# Top.net
KiCad netlist of a schematic drawn in Altium Designer
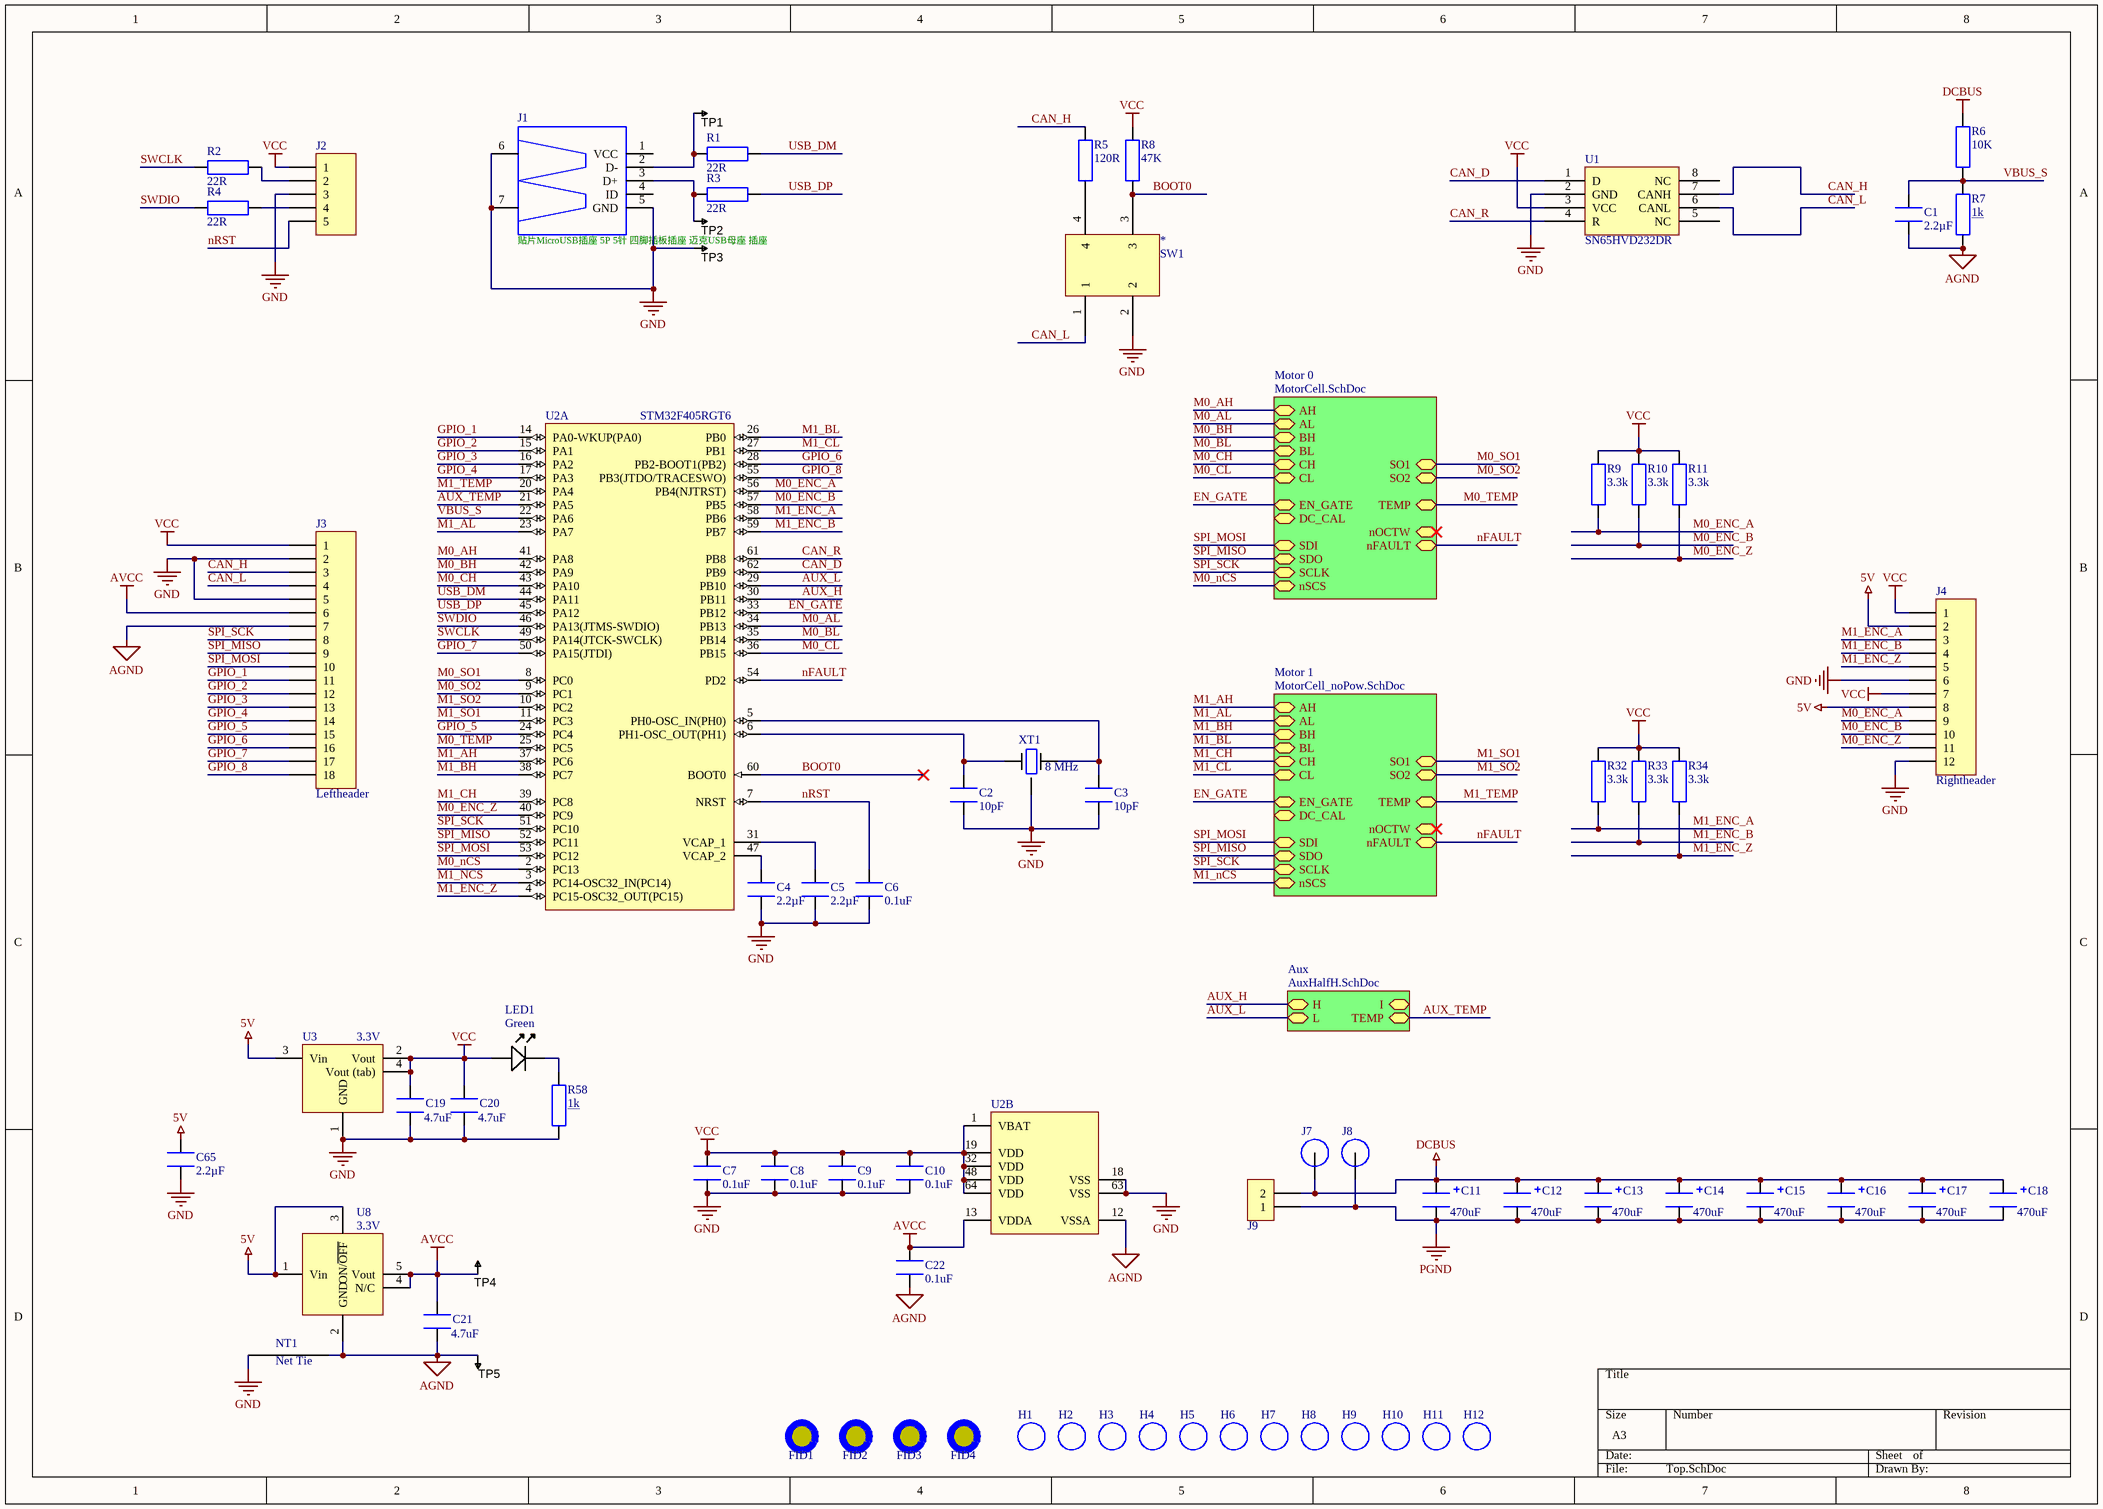
[diagram p0: Top.SchDoc]

(export (version "E")
  (design (tool "Eeschema 10.0.6"))
  (components
    (comp (ref "*")
      (value "SW1")
      (footprint "switch_2")
      (libsource (lib "CustomComponents") (part "Switch_2"))
    )
    (comp (ref "C1")
      (value "2.2µF")
      (footprint "CAPC1608X09L")
      (description "CAP CER 2.2UF 16V X5R 0603")
      (fields
        (field (name "MANUFACTURER") "Murata Electronics North America")
        (field (name "MANUFACTURER PART NUMBER") "GRM188R61C225KE15D")
      )
      (libsource (lib "CustomComponents") (part "GRM188R61C225KE15D"))
    )
    (comp (ref "C2")
      (value "10pF")
      (footprint "CAPC1608X09L")
      (description "CAP CER 10PF 50V NP0 0603")
      (fields
        (field (name "MANUFACTURER") "Murata Electronics North America")
        (field (name "MANUFACTURER PART NUMBER") "GRM1885C1H100JA01D")
      )
      (libsource (lib "CustomComponents") (part "GRM1885C1H100JA01D"))
    )
    (comp (ref "C3")
      (value "10pF")
      (footprint "CAPC1608X09L")
      (description "CAP CER 10PF 50V NP0 0603")
      (fields
        (field (name "MANUFACTURER") "Murata Electronics North America")
        (field (name "MANUFACTURER PART NUMBER") "GRM1885C1H100JA01D")
      )
      (libsource (lib "CustomComponents") (part "GRM1885C1H100JA01D"))
    )
    (comp (ref "C4")
      (value "2.2µF")
      (footprint "CAPC1608X09L")
      (description "CAP CER 2.2UF 16V X5R 0603")
      (fields
        (field (name "MANUFACTURER") "Murata Electronics North America")
        (field (name "MANUFACTURER PART NUMBER") "GRM188R61C225KE15D")
      )
      (libsource (lib "CustomComponents") (part "GRM188R61C225KE15D"))
    )
    (comp (ref "C5")
      (value "2.2µF")
      (footprint "CAPC1608X09L")
      (description "CAP CER 2.2UF 16V X5R 0603")
      (fields
        (field (name "MANUFACTURER") "Murata Electronics North America")
        (field (name "MANUFACTURER PART NUMBER") "GRM188R61C225KE15D")
      )
      (libsource (lib "CustomComponents") (part "GRM188R61C225KE15D"))
    )
    (comp (ref "C6")
      (value "0.1uF")
      (footprint "CAPC1608X09L")
      (description "CAP CER 0.1UF 50V X7R 0603")
      (fields
        (field (name "MANUFACTURER") "Murata Electronics North America")
        (field (name "MANUFACTURER PART NUMBER") "GRM188R71H104KA93D")
      )
      (libsource (lib "CustomComponents") (part "GRM188R71H104KA93D"))
    )
    (comp (ref "C7")
      (value "0.1uF")
      (footprint "CAPC1608X09L")
      (description "CAP CER 0.1UF 50V X7R 0603")
      (fields
        (field (name "MANUFACTURER") "Murata Electronics North America")
        (field (name "MANUFACTURER PART NUMBER") "GRM188R71H104KA93D")
      )
      (libsource (lib "CustomComponents") (part "GRM188R71H104KA93D"))
    )
    (comp (ref "C8")
      (value "0.1uF")
      (footprint "CAPC1608X09L")
      (description "CAP CER 0.1UF 50V X7R 0603")
      (fields
        (field (name "MANUFACTURER") "Murata Electronics North America")
        (field (name "MANUFACTURER PART NUMBER") "GRM188R71H104KA93D")
      )
      (libsource (lib "CustomComponents") (part "GRM188R71H104KA93D"))
    )
    (comp (ref "C9")
      (value "0.1uF")
      (footprint "CAPC1608X09L")
      (description "CAP CER 0.1UF 50V X7R 0603")
      (fields
        (field (name "MANUFACTURER") "Murata Electronics North America")
        (field (name "MANUFACTURER PART NUMBER") "GRM188R71H104KA93D")
      )
      (libsource (lib "CustomComponents") (part "GRM188R71H104KA93D"))
    )
    (comp (ref "C10")
      (value "0.1uF")
      (footprint "CAPC1608X09L")
      (description "CAP CER 0.1UF 50V X7R 0603")
      (fields
        (field (name "MANUFACTURER") "Murata Electronics North America")
        (field (name "MANUFACTURER PART NUMBER") "GRM188R71H104KA93D")
      )
      (libsource (lib "CustomComponents") (part "GRM188R71H104KA93D"))
    )
    (comp (ref "C11")
      (value "470uF")
      (footprint "CAP_ELEC_SIZE_G")
      (description "CAP, FP Series, 470 µF, 25 V, Radial Can - SMD, 10 mm")
      (fields
        (field (name "MANUFACTURER") "Panasonic Electronic Components")
        (field (name "TOLERANCE") "?0%")
      )
      (libsource (lib "CustomComponents") (part "EEEFP1E471AP"))
    )
    (comp (ref "C12")
      (value "470uF")
      (footprint "CAP_ELEC_SIZE_G")
      (description "CAP, FP Series, 470 µF, 25 V, Radial Can - SMD, 10 mm")
      (fields
        (field (name "MANUFACTURER") "Panasonic Electronic Components")
        (field (name "TOLERANCE") "?0%")
      )
      (libsource (lib "CustomComponents") (part "EEEFP1E471AP"))
    )
    (comp (ref "C13")
      (value "470uF")
      (footprint "CAP_ELEC_SIZE_G")
      (description "CAP, FP Series, 470 µF, 25 V, Radial Can - SMD, 10 mm")
      (fields
        (field (name "MANUFACTURER") "Panasonic Electronic Components")
        (field (name "TOLERANCE") "?0%")
      )
      (libsource (lib "CustomComponents") (part "EEEFP1E471AP"))
    )
    (comp (ref "C14")
      (value "470uF")
      (footprint "CAP_ELEC_SIZE_G")
      (description "CAP, FP Series, 470 µF, 25 V, Radial Can - SMD, 10 mm")
      (fields
        (field (name "MANUFACTURER") "Panasonic Electronic Components")
        (field (name "TOLERANCE") "?0%")
      )
      (libsource (lib "CustomComponents") (part "EEEFP1E471AP"))
    )
    (comp (ref "C15")
      (value "470uF")
      (footprint "CAP_ELEC_SIZE_G")
      (description "CAP, FP Series, 470 µF, 25 V, Radial Can - SMD, 10 mm")
      (fields
        (field (name "MANUFACTURER") "Panasonic Electronic Components")
        (field (name "TOLERANCE") "?0%")
      )
      (libsource (lib "CustomComponents") (part "EEEFP1E471AP"))
    )
    (comp (ref "C16")
      (value "470uF")
      (footprint "CAP_ELEC_SIZE_G")
      (description "CAP, FP Series, 470 µF, 25 V, Radial Can - SMD, 10 mm")
      (fields
        (field (name "MANUFACTURER") "Panasonic Electronic Components")
        (field (name "TOLERANCE") "?0%")
      )
      (libsource (lib "CustomComponents") (part "EEEFP1E471AP"))
    )
    (comp (ref "C17")
      (value "470uF")
      (footprint "CAP_ELEC_SIZE_G")
      (description "CAP, FP Series, 470 µF, 25 V, Radial Can - SMD, 10 mm")
      (fields
        (field (name "MANUFACTURER") "Panasonic Electronic Components")
        (field (name "TOLERANCE") "?0%")
      )
      (libsource (lib "CustomComponents") (part "EEEFP1E471AP"))
    )
    (comp (ref "C18")
      (value "470uF")
      (footprint "CAP_ELEC_SIZE_G")
      (description "CAP, FP Series, 470 µF, 25 V, Radial Can - SMD, 10 mm")
      (fields
        (field (name "MANUFACTURER") "Panasonic Electronic Components")
        (field (name "TOLERANCE") "?0%")
      )
      (libsource (lib "CustomComponents") (part "EEEFP1E471AP"))
    )
    (comp (ref "C19")
      (value "4.7uF")
      (footprint "CAPC2012X09N")
      (description "CAP CER 4.7UF 35V X5R 0805")
      (fields
        (field (name "MANUFACTURER") "Murata Electronics North America")
        (field (name "TOLERANCE") "?0%")
      )
      (libsource (lib "CustomComponents") (part "GRM219R6YA475KA73D"))
    )
    (comp (ref "C20")
      (value "4.7uF")
      (footprint "CAPC2012X09N")
      (description "CAP CER 4.7UF 35V X5R 0805")
      (fields
        (field (name "MANUFACTURER") "Murata Electronics North America")
        (field (name "TOLERANCE") "?0%")
      )
      (libsource (lib "CustomComponents") (part "GRM219R6YA475KA73D"))
    )
    (comp (ref "C21")
      (value "4.7uF")
      (footprint "CAPC2012X09N")
      (description "CAP CER 4.7UF 35V X5R 0805")
      (fields
        (field (name "MANUFACTURER") "Murata Electronics North America")
        (field (name "TOLERANCE") "?0%")
      )
      (libsource (lib "CustomComponents") (part "GRM219R6YA475KA73D"))
    )
    (comp (ref "C22")
      (value "0.1uF")
      (footprint "CAPC1608X09L")
      (description "CAP CER 0.1UF 50V X7R 0603")
      (fields
        (field (name "MANUFACTURER") "Murata Electronics North America")
        (field (name "MANUFACTURER PART NUMBER") "GRM188R71H104KA93D")
      )
      (libsource (lib "CustomComponents") (part "GRM188R71H104KA93D"))
    )
    (comp (ref "C65")
      (value "2.2µF")
      (footprint "CAPC1608X09L")
      (description "CAP CER 2.2UF 16V X5R 0603")
      (fields
        (field (name "MANUFACTURER") "Murata Electronics North America")
        (field (name "MANUFACTURER PART NUMBER") "GRM188R61C225KE15D")
      )
      (libsource (lib "CustomComponents") (part "GRM188R61C225KE15D"))
    )
    (comp (ref "FID1")
      (value "FIDUCIAL")
      (footprint "FIDUCIAL")
      (description "1mm Fiducial with 2mm soldermask, 3mm keepout")
      (libsource (lib "CustomComponents") (part "FIDUCIAL"))
    )
    (comp (ref "FID2")
      (value "FIDUCIAL")
      (footprint "FIDUCIAL")
      (description "1mm Fiducial with 2mm soldermask, 3mm keepout")
      (libsource (lib "CustomComponents") (part "FIDUCIAL"))
    )
    (comp (ref "FID3")
      (value "FIDUCIAL")
      (footprint "FIDUCIAL")
      (description "1mm Fiducial with 2mm soldermask, 3mm keepout")
      (libsource (lib "CustomComponents") (part "FIDUCIAL"))
    )
    (comp (ref "FID4")
      (value "FIDUCIAL")
      (footprint "FIDUCIAL")
      (description "1mm Fiducial with 2mm soldermask, 3mm keepout")
      (libsource (lib "CustomComponents") (part "FIDUCIAL"))
    )
    (comp (ref "H1")
      (value "~")
      (footprint "M3 Hole")
      (description "M3 Hole with no copper")
      (libsource (lib "CustomComponents") (part "M3 Hole"))
    )
    (comp (ref "H2")
      (value "~")
      (footprint "M3 Hole")
      (description "M3 Hole with no copper")
      (libsource (lib "CustomComponents") (part "M3 Hole"))
    )
    (comp (ref "H3")
      (value "~")
      (footprint "M3 Hole")
      (description "M3 Hole with no copper")
      (libsource (lib "CustomComponents") (part "M3 Hole"))
    )
    (comp (ref "H4")
      (value "~")
      (footprint "M3 Hole")
      (description "M3 Hole with no copper")
      (libsource (lib "CustomComponents") (part "M3 Hole"))
    )
    (comp (ref "H5")
      (value "~")
      (footprint "M3 Hole")
      (description "M3 Hole with no copper")
      (libsource (lib "CustomComponents") (part "M3 Hole"))
    )
    (comp (ref "H6")
      (value "~")
      (footprint "M3 Hole")
      (description "M3 Hole with no copper")
      (libsource (lib "CustomComponents") (part "M3 Hole"))
    )
    (comp (ref "H7")
      (value "~")
      (footprint "M3 Hole")
      (description "M3 Hole with no copper")
      (libsource (lib "CustomComponents") (part "M3 Hole"))
    )
    (comp (ref "H8")
      (value "~")
      (footprint "M3 Hole")
      (description "M3 Hole with no copper")
      (libsource (lib "CustomComponents") (part "M3 Hole"))
    )
    (comp (ref "H9")
      (value "~")
      (footprint "M3 Hole")
      (description "M3 Hole with no copper")
      (libsource (lib "CustomComponents") (part "M3 Hole"))
    )
    (comp (ref "H10")
      (value "~")
      (footprint "M3 Hole")
      (description "M3 Hole with no copper")
      (libsource (lib "CustomComponents") (part "M3 Hole"))
    )
    (comp (ref "H11")
      (value "~")
      (footprint "M3 Hole")
      (description "M3 Hole with no copper")
      (libsource (lib "CustomComponents") (part "M3 Hole"))
    )
    (comp (ref "H12")
      (value "~")
      (footprint "M3 Hole")
      (description "M3 Hole with no copper")
      (libsource (lib "CustomComponents") (part "M3 Hole"))
    )
    (comp (ref "J1")
      (value "贴片MicroUSB插座 5P 5针 四脚插板插座 迈克USB母座 插座")
      (footprint "Micro_USB")
      (libsource (lib "*") (part "USB_1_1"))
    )
    (comp (ref "J2")
      (value "~")
      (footprint "HDR1X5")
      (description "Header, 5-Pin")
      (fields (field (name "PUBLISHER") "Altium Limited"))
      (libsource (lib "Miscellaneous Connectors") (part "Header 5"))
    )
    (comp (ref "J3")
      (value "Leftheader")
      (footprint "HDR1X18")
      (description "Header, 18-Pin")
      (fields (field (name "PUBLISHER") "Altium Limited"))
      (libsource (lib "Miscellaneous Connectors") (part "Header 18"))
    )
    (comp (ref "J4")
      (value "Rightheader")
      (footprint "HDR1X12")
      (description "Header, 12-Pin")
      (fields (field (name "PUBLISHER") "Altium Limited"))
      (libsource (lib "Miscellaneous Connectors") (part "Header 12"))
    )
    (comp (ref "J7")
      (value "~")
      (footprint "M3 Spade Hole")
      (description "M3 Spade Terminal")
      (libsource (lib "CustomComponents") (part "M3 Spade Terminal"))
    )
    (comp (ref "J8")
      (value "~")
      (footprint "M3 Spade Hole")
      (description "M3 Spade Terminal")
      (libsource (lib "CustomComponents") (part "M3 Spade Terminal"))
    )
    (comp (ref "J9")
      (value "1868076")
      (footprint "1868076")
      (description "CONN TERM BLOCK 2POS 7.62MM")
      (fields (field (name "MANUFACTURER") "Phoenix Contact") (field (name "VOLTAGE") "300V"))
      (libsource (lib "CustomComponents") (part "1868076"))
    )
    (comp (ref "LED1")
      (value "Green")
      (footprint "LED-0603-GREEN")
      (description "LED GREEN CLEAR 0603 SMD")
      (fields
        (field (name "MANUFACTURER") "Lite-On Inc.")
        (field (name "MANUFACTURER PART NUMBER") "LTST-C190KGKT")
      )
      (libsource (lib "CustomComponents") (part "LTST-C190KGKT"))
    )
    (comp (ref "NT1")
      (value "~")
      (footprint "NetTie_2mm")
      (libsource (lib "CustomComponents") (part "NetTie_2mm"))
    )
    (comp (ref "R1")
      (value "22R")
      (footprint "RESC1608X55N")
      (description "RES SMD 22 OHM 1% 1/10W 0603")
      (fields
        (field (name "MANUFACTURER") "Yageo")
        (field (name "MANUFACTURER PART NUMBER") "RC0603FR-0722RL")
      )
      (libsource (lib "CustomComponents") (part "RC0603FR-0722RL"))
    )
    (comp (ref "R2")
      (value "22R")
      (footprint "RESC1608X55N")
      (description "RES SMD 22 OHM 1% 1/10W 0603")
      (fields
        (field (name "MANUFACTURER") "Yageo")
        (field (name "MANUFACTURER PART NUMBER") "RC0603FR-0722RL")
      )
      (libsource (lib "CustomComponents") (part "RC0603FR-0722RL"))
    )
    (comp (ref "R3")
      (value "22R")
      (footprint "RESC1608X55N")
      (description "RES SMD 22 OHM 1% 1/10W 0603")
      (fields
        (field (name "MANUFACTURER") "Yageo")
        (field (name "MANUFACTURER PART NUMBER") "RC0603FR-0722RL")
      )
      (libsource (lib "CustomComponents") (part "RC0603FR-0722RL"))
    )
    (comp (ref "R4")
      (value "22R")
      (footprint "RESC1608X55N")
      (description "RES SMD 22 OHM 1% 1/10W 0603")
      (fields
        (field (name "MANUFACTURER") "Yageo")
        (field (name "MANUFACTURER PART NUMBER") "RC0603FR-0722RL")
      )
      (libsource (lib "CustomComponents") (part "RC0603FR-0722RL"))
    )
    (comp (ref "R5")
      (value "120R")
      (footprint "RESC1608X55N")
      (description "RES SMD 120 OHM 1% 1/10W 0603")
      (fields
        (field (name "MANUFACTURER") "Yageo")
        (field (name "MANUFACTURER PART NUMBER") "RC0603FR-07120RL")
      )
      (libsource (lib "CustomComponents") (part "RC0603FR-07120RL"))
    )
    (comp (ref "R6")
      (value "10K")
      (footprint "RESC1608X55N")
      (description "RES SMD 10K OHM 1% 1/10W 0603")
      (fields
        (field (name "MANUFACTURER") "Yageo")
        (field (name "MANUFACTURER PART NUMBER") "RC0603FR-0710KL")
      )
      (libsource (lib "CustomComponents") (part "RC0603FR-0710KL"))
    )
    (comp (ref "R7")
      (value "1k")
      (footprint "RESC1608X55N")
      (description "RES SMD 1K OHM 1% 1/10W 0603")
      (fields (field (name "MANUFACTURER") "Yageo") (field (name "TOLERANCE") "?%"))
      (libsource (lib "CustomComponents") (part "RC0603FR-071KL"))
    )
    (comp (ref "R8")
      (value "47K")
      (footprint "RESC1608X55N")
      (description "RES SMD 47K OHM 1% 1/10W 0603")
      (fields
        (field (name "MANUFACTURER") "Yageo")
        (field (name "MANUFACTURER PART NUMBER") "RC0603FR-0747KL")
      )
      (libsource (lib "CustomComponents") (part "RC0603FR-0747KL"))
    )
    (comp (ref "R9")
      (value "3.3k")
      (footprint "RESC1608X55N")
      (description "RES SMD 3.3K OHM 1% 1/10W 0603")
      (fields (field (name "MANUFACTURER") "Yageo") (field (name "TOLERANCE") "?%"))
      (libsource (lib "CustomComponents") (part "RC0603FR-073K3L"))
    )
    (comp (ref "R10")
      (value "3.3k")
      (footprint "RESC1608X55N")
      (description "RES SMD 3.3K OHM 1% 1/10W 0603")
      (fields (field (name "MANUFACTURER") "Yageo") (field (name "TOLERANCE") "?%"))
      (libsource (lib "CustomComponents") (part "RC0603FR-073K3L"))
    )
    (comp (ref "R11")
      (value "3.3k")
      (footprint "RESC1608X55N")
      (description "RES SMD 3.3K OHM 1% 1/10W 0603")
      (fields (field (name "MANUFACTURER") "Yageo") (field (name "TOLERANCE") "?%"))
      (libsource (lib "CustomComponents") (part "RC0603FR-073K3L"))
    )
    (comp (ref "R32")
      (value "3.3k")
      (footprint "RESC1608X55N")
      (description "RES SMD 3.3K OHM 1% 1/10W 0603")
      (fields (field (name "MANUFACTURER") "Yageo") (field (name "TOLERANCE") "?%"))
      (libsource (lib "CustomComponents") (part "RC0603FR-073K3L"))
    )
    (comp (ref "R33")
      (value "3.3k")
      (footprint "RESC1608X55N")
      (description "RES SMD 3.3K OHM 1% 1/10W 0603")
      (fields (field (name "MANUFACTURER") "Yageo") (field (name "TOLERANCE") "?%"))
      (libsource (lib "CustomComponents") (part "RC0603FR-073K3L"))
    )
    (comp (ref "R34")
      (value "3.3k")
      (footprint "RESC1608X55N")
      (description "RES SMD 3.3K OHM 1% 1/10W 0603")
      (fields (field (name "MANUFACTURER") "Yageo") (field (name "TOLERANCE") "?%"))
      (libsource (lib "CustomComponents") (part "RC0603FR-073K3L"))
    )
    (comp (ref "R58")
      (value "1k")
      (footprint "RESC1608X55N")
      (description "RES SMD 1K OHM 1% 1/10W 0603")
      (fields (field (name "MANUFACTURER") "Yageo") (field (name "TOLERANCE") "?%"))
      (libsource (lib "CustomComponents") (part "RC0603FR-071KL"))
    )
    (comp (ref "TP1")
      (value "TESTPOINT")
      (footprint "TP-R60")
      (description "SMD test pin")
      (libsource (lib "PBL - Test Points") (part "TESTPOINT"))
    )
    (comp (ref "TP2")
      (value "TESTPOINT")
      (footprint "TP-R60")
      (description "SMD test pin")
      (libsource (lib "PBL - Test Points") (part "TESTPOINT"))
    )
    (comp (ref "TP3")
      (value "TESTPOINT")
      (footprint "TP-R60")
      (description "SMD test pin")
      (libsource (lib "PBL - Test Points") (part "TESTPOINT"))
    )
    (comp (ref "TP4")
      (value "TESTPOINT")
      (footprint "TP-R30")
      (description "SMD test pin")
      (libsource (lib "PBL - Test Points") (part "TESTPOINT"))
    )
    (comp (ref "TP5")
      (value "TESTPOINT")
      (footprint "TP-R30")
      (description "SMD test pin")
      (libsource (lib "PBL - Test Points") (part "TESTPOINT"))
    )
    (comp (ref "U1")
      (value "SN65HVD232D")
      (footprint "SOIC127P600X175-8N")
      (fields
        (field (name "MANUFACTURER") "Texas Instruments")
        (field (name "MANUFACTURER PART NUMBER") "SN65HVD232DR")
      )
      (libsource (lib "CustomComponents") (part "SN65HVD232D"))
    )
    (comp (ref "U2")
      (value "~")
      (footprint "STM-LQFP64_N")
      (fields (field (name "MANUFACTURER") "STMicroelectronics") (field (name "PARTNUMBER") "STM32F405RGT6"))
      (libsource (lib "STMicroelectronics STM32 F4") (part "STM32F405RGT6"))
    )
    (comp (ref "U3")
      (value "3.3V")
      (footprint "SOT223")
      (description "IC REG LDO 3.3V 1A SOT223")
      (fields (field (name "MANUFACTURER") "Diodes Incorporated"))
      (libsource (lib "CustomComponents") (part "AZ1117EH-3.3TRG1"))
    )
    (comp (ref "U8")
      (value "3.3V")
      (footprint "SOT23-5")
      (description "IC REG LDO 3.3V 0.25A SOT23-5")
      (fields (field (name "MANUFACTURER") "Texas Instruments"))
      (libsource (lib "CustomComponents") (part "LP5907MFX-3.3/NOPB"))
    )
    (comp (ref "XT1")
      (value "8 MHz")
      (footprint "DFN220P320X110-4N")
      (description "Crystal 8MHz ?0ppm 10pF 200 Ohm -10°C ~ 60°C Surface Mount 4-SMD, No Lead (DFN, LCC)")
      (fields
        (field (name "MANUFACTURER") "Abracon LLC")
        (field (name "MANUFACTURER PART NUMBER") "ABM3B-8.000MHZ-10-1-U-T")
      )
      (libsource (lib "CustomComponents") (part "ABM3B-8.000MHZ-10-1-U-T"))
    )
  )
  (nets
    (net (code "1") (name "/AUX_H") (class "Default")
      (node (ref "U2") (pin "30") (pinfunction "PB11_30") (pintype "bidirectional"))
    )
    (net (code "2") (name "/AUX_L") (class "Default")
      (node (ref "U2") (pin "29") (pinfunction "PB10_29") (pintype "bidirectional"))
    )
    (net (code "3") (name "/AUX_TEMP") (class "Default")
      (node (ref "U2") (pin "21") (pinfunction "PA5_21") (pintype "bidirectional"))
    )
    (net (code "4") (name "/BOOT0") (class "Default")
      (node (ref "*") (pin "3") (pinfunction "3_3") (pintype "passive"))
      (node (ref "R8") (pin "1") (pinfunction "0_1") (pintype "passive"))
      (node (ref "U2") (pin "60") (pinfunction "BOOT0_60") (pintype "input"))
    )
    (net (code "5") (name "/CAN_D") (class "Default")
      (node (ref "U1") (pin "1") (pinfunction "D_1") (pintype "passive"))
      (node (ref "U2") (pin "62") (pinfunction "PB9_62") (pintype "bidirectional"))
    )
    (net (code "6") (name "/CAN_H") (class "Default")
      (node (ref "J3") (pin "3") (pinfunction "3_3") (pintype "passive"))
      (node (ref "R5") (pin "2") (pinfunction "0_2") (pintype "passive"))
      (node (ref "U1") (pin "7") (pinfunction "CANH_7") (pintype "passive"))
    )
    (net (code "7") (name "/CAN_L") (class "Default")
      (node (ref "*") (pin "1") (pinfunction "1_1") (pintype "passive"))
      (node (ref "J3") (pin "4") (pinfunction "4_4") (pintype "passive"))
      (node (ref "U1") (pin "6") (pinfunction "CANL_6") (pintype "passive"))
    )
    (net (code "8") (name "/CAN_R") (class "Default")
      (node (ref "U1") (pin "4") (pinfunction "R_4") (pintype "passive"))
      (node (ref "U2") (pin "61") (pinfunction "PB8_61") (pintype "bidirectional"))
    )
    (net (code "11") (name "/EN_GATE") (class "Default")
      (node (ref "U2") (pin "33") (pinfunction "PB12_33") (pintype "bidirectional"))
    )
    (net (code "12") (name "/GPIO_1") (class "Default")
      (node (ref "J3") (pin "11") (pinfunction "11_11") (pintype "passive"))
      (node (ref "U2") (pin "14") (pinfunction "PA0-WKUP(PA0)_14") (pintype "bidirectional"))
    )
    (net (code "13") (name "/GPIO_2") (class "Default")
      (node (ref "J3") (pin "12") (pinfunction "12_12") (pintype "passive"))
      (node (ref "U2") (pin "15") (pinfunction "PA1_15") (pintype "bidirectional"))
    )
    (net (code "14") (name "/GPIO_3") (class "Default")
      (node (ref "J3") (pin "13") (pinfunction "13_13") (pintype "passive"))
      (node (ref "U2") (pin "16") (pinfunction "PA2_16") (pintype "bidirectional"))
    )
    (net (code "15") (name "/GPIO_4") (class "Default")
      (node (ref "J3") (pin "14") (pinfunction "14_14") (pintype "passive"))
      (node (ref "U2") (pin "17") (pinfunction "PA3_17") (pintype "bidirectional"))
    )
    (net (code "16") (name "/GPIO_5") (class "Default")
      (node (ref "J3") (pin "15") (pinfunction "15_15") (pintype "passive"))
      (node (ref "U2") (pin "24") (pinfunction "PC4_24") (pintype "bidirectional"))
    )
    (net (code "17") (name "/GPIO_6") (class "Default")
      (node (ref "J3") (pin "16") (pinfunction "16_16") (pintype "passive"))
      (node (ref "U2") (pin "28") (pinfunction "PB2-BOOT1(PB2)_28") (pintype "bidirectional"))
    )
    (net (code "18") (name "/GPIO_7") (class "Default")
      (node (ref "J3") (pin "17") (pinfunction "17_17") (pintype "passive"))
      (node (ref "U2") (pin "50") (pinfunction "PA15(JTDI)_50") (pintype "bidirectional"))
    )
    (net (code "19") (name "/GPIO_8") (class "Default")
      (node (ref "J3") (pin "18") (pinfunction "18_18") (pintype "passive"))
      (node (ref "U2") (pin "55") (pinfunction "PB3(JTDO/TRACESWO)_55") (pintype "bidirectional"))
    )
    (net (code "21") (name "/M0_AH") (class "Default")
      (node (ref "U2") (pin "41") (pinfunction "PA8_41") (pintype "bidirectional"))
    )
    (net (code "22") (name "/M0_AL") (class "Default")
      (node (ref "U2") (pin "34") (pinfunction "PB13_34") (pintype "bidirectional"))
    )
    (net (code "23") (name "/M0_BH") (class "Default")
      (node (ref "U2") (pin "42") (pinfunction "PA9_42") (pintype "bidirectional"))
    )
    (net (code "24") (name "/M0_BL") (class "Default")
      (node (ref "U2") (pin "35") (pinfunction "PB14_35") (pintype "bidirectional"))
    )
    (net (code "25") (name "/M0_CH") (class "Default")
      (node (ref "U2") (pin "43") (pinfunction "PA10_43") (pintype "bidirectional"))
    )
    (net (code "26") (name "/M0_CL") (class "Default")
      (node (ref "U2") (pin "36") (pinfunction "PB15_36") (pintype "bidirectional"))
    )
    (net (code "27") (name "/M0_ENC_A") (class "Default")
      (node (ref "J4") (pin "9") (pinfunction "9_9") (pintype "passive"))
      (node (ref "R9") (pin "1") (pinfunction "0_1") (pintype "passive"))
      (node (ref "U2") (pin "56") (pinfunction "PB4(NJTRST)_56") (pintype "bidirectional"))
    )
    (net (code "28") (name "/M0_ENC_B") (class "Default")
      (node (ref "J4") (pin "10") (pinfunction "10_10") (pintype "passive"))
      (node (ref "R10") (pin "1") (pinfunction "0_1") (pintype "passive"))
      (node (ref "U2") (pin "57") (pinfunction "PB5_57") (pintype "bidirectional"))
    )
    (net (code "29") (name "/M0_ENC_Z") (class "Default")
      (node (ref "J4") (pin "11") (pinfunction "11_11") (pintype "passive"))
      (node (ref "R11") (pin "1") (pinfunction "0_1") (pintype "passive"))
      (node (ref "U2") (pin "40") (pinfunction "PC9_40") (pintype "bidirectional"))
    )
    (net (code "30") (name "/M0_SO1") (class "Default")
      (node (ref "U2") (pin "8") (pinfunction "PC0_8") (pintype "bidirectional"))
    )
    (net (code "31") (name "/M0_SO2") (class "Default")
      (node (ref "U2") (pin "9") (pinfunction "PC1_9") (pintype "bidirectional"))
    )
    (net (code "32") (name "/M0_TEMP") (class "Default")
      (node (ref "U2") (pin "25") (pinfunction "PC5_25") (pintype "bidirectional"))
    )
    (net (code "33") (name "/M0_nCS") (class "Default")
      (node (ref "U2") (pin "2") (pinfunction "PC13_2") (pintype "bidirectional"))
    )
    (net (code "34") (name "/M1_AH") (class "Default")
      (node (ref "U2") (pin "37") (pinfunction "PC6_37") (pintype "bidirectional"))
    )
    (net (code "35") (name "/M1_AL") (class "Default")
      (node (ref "U2") (pin "23") (pinfunction "PA7_23") (pintype "bidirectional"))
    )
    (net (code "36") (name "/M1_BH") (class "Default")
      (node (ref "U2") (pin "38") (pinfunction "PC7_38") (pintype "bidirectional"))
    )
    (net (code "37") (name "/M1_BL") (class "Default")
      (node (ref "U2") (pin "26") (pinfunction "PB0_26") (pintype "bidirectional"))
    )
    (net (code "38") (name "/M1_CH") (class "Default")
      (node (ref "U2") (pin "39") (pinfunction "PC8_39") (pintype "bidirectional"))
    )
    (net (code "39") (name "/M1_CL") (class "Default")
      (node (ref "U2") (pin "27") (pinfunction "PB1_27") (pintype "bidirectional"))
    )
    (net (code "40") (name "/M1_ENC_A") (class "Default")
      (node (ref "J4") (pin "3") (pinfunction "3_3") (pintype "passive"))
      (node (ref "R32") (pin "2") (pinfunction "0_2") (pintype "passive"))
      (node (ref "U2") (pin "58") (pinfunction "PB6_58") (pintype "bidirectional"))
    )
    (net (code "41") (name "/M1_ENC_B") (class "Default")
      (node (ref "J4") (pin "4") (pinfunction "4_4") (pintype "passive"))
      (node (ref "R33") (pin "2") (pinfunction "0_2") (pintype "passive"))
      (node (ref "U2") (pin "59") (pinfunction "PB7_59") (pintype "bidirectional"))
    )
    (net (code "42") (name "/M1_ENC_Z") (class "Default")
      (node (ref "J4") (pin "5") (pinfunction "5_5") (pintype "passive"))
      (node (ref "R34") (pin "2") (pinfunction "0_2") (pintype "passive"))
      (node (ref "U2") (pin "4") (pinfunction "PC15-OSC32_OUT(PC15)_4") (pintype "bidirectional"))
    )
    (net (code "43") (name "/M1_NCS") (class "Default")
      (node (ref "U2") (pin "3") (pinfunction "PC14-OSC32_IN(PC14)_3") (pintype "bidirectional"))
    )
    (net (code "44") (name "/M1_SO1") (class "Default")
      (node (ref "U2") (pin "11") (pinfunction "PC3_11") (pintype "bidirectional"))
    )
    (net (code "45") (name "/M1_SO2") (class "Default")
      (node (ref "U2") (pin "10") (pinfunction "PC2_10") (pintype "bidirectional"))
    )
    (net (code "46") (name "/M1_TEMP") (class "Default")
      (node (ref "U2") (pin "20") (pinfunction "PA4_20") (pintype "bidirectional"))
    )
    (net (code "48") (name "/SPI_MISO") (class "Default")
      (node (ref "J3") (pin "9") (pinfunction "9_9") (pintype "passive"))
      (node (ref "U2") (pin "52") (pinfunction "PC11_52") (pintype "bidirectional"))
    )
    (net (code "49") (name "/SPI_MOSI") (class "Default")
      (node (ref "J3") (pin "10") (pinfunction "10_10") (pintype "passive"))
      (node (ref "U2") (pin "53") (pinfunction "PC12_53") (pintype "bidirectional"))
    )
    (net (code "50") (name "/SPI_SCK") (class "Default")
      (node (ref "J3") (pin "8") (pinfunction "8_8") (pintype "passive"))
      (node (ref "U2") (pin "51") (pinfunction "PC10_51") (pintype "bidirectional"))
    )
    (net (code "51") (name "/SWCLK") (class "Default")
      (node (ref "R2") (pin "2") (pinfunction "0_2") (pintype "passive"))
      (node (ref "U2") (pin "49") (pinfunction "PA14(JTCK-SWCLK)_49") (pintype "bidirectional"))
    )
    (net (code "52") (name "/SWDIO") (class "Default")
      (node (ref "R4") (pin "2") (pinfunction "0_2") (pintype "passive"))
      (node (ref "U2") (pin "46") (pinfunction "PA13(JTMS-SWDIO)_46") (pintype "bidirectional"))
    )
    (net (code "53") (name "/USB_DM") (class "Default")
      (node (ref "R1") (pin "1") (pinfunction "0_1") (pintype "passive"))
      (node (ref "U2") (pin "44") (pinfunction "PA11_44") (pintype "bidirectional"))
    )
    (net (code "54") (name "/USB_DP") (class "Default")
      (node (ref "R3") (pin "1") (pinfunction "0_1") (pintype "passive"))
      (node (ref "U2") (pin "45") (pinfunction "PA12_45") (pintype "bidirectional"))
    )
    (net (code "55") (name "/VBUS_S") (class "Default")
      (node (ref "C1") (pin "2") (pinfunction "2_2") (pintype "passive"))
      (node (ref "R6") (pin "1") (pinfunction "0_1") (pintype "passive"))
      (node (ref "R7") (pin "2") (pinfunction "0_2") (pintype "passive"))
      (node (ref "U2") (pin "22") (pinfunction "PA6_22") (pintype "bidirectional"))
    )
    (net (code "56") (name "/nFAULT") (class "Default")
      (node (ref "U2") (pin "54") (pinfunction "PD2_54") (pintype "bidirectional"))
    )
    (net (code "59") (name "/nRST") (class "Default")
      (node (ref "C6") (pin "2") (pinfunction "2_2") (pintype "passive"))
      (node (ref "J2") (pin "5") (pinfunction "5_5") (pintype "passive"))
      (node (ref "U2") (pin "7") (pinfunction "NRST_7") (pintype "bidirectional"))
    )
    (net (code "60") (name "5V") (class "Default")
      (node (ref "C65") (pin "2") (pinfunction "2_2") (pintype "passive"))
      (node (ref "J4") (pin "2") (pinfunction "2_2") (pintype "passive"))
      (node (ref "J4") (pin "8") (pinfunction "8_8") (pintype "passive"))
      (node (ref "U3") (pin "3") (pinfunction "Vin_3") (pintype "passive"))
      (node (ref "U8") (pin "1") (pinfunction "Vin_1") (pintype "passive"))
      (node (ref "U8") (pin "3") (pinfunction "ON/~{OFF}_3") (pintype "passive"))
    )
    (net (code "61") (name "AGND") (class "Default")
      (node (ref "C1") (pin "1") (pinfunction "1_1") (pintype "passive"))
      (node (ref "C21") (pin "1") (pinfunction "1_1") (pintype "passive"))
      (node (ref "C22") (pin "2") (pinfunction "2_2") (pintype "passive"))
      (node (ref "J3") (pin "7") (pinfunction "7_7") (pintype "passive"))
      (node (ref "NT1") (pin "2") (pintype "passive"))
      (node (ref "R7") (pin "1") (pinfunction "0_1") (pintype "passive"))
      (node (ref "TP5") (pin "1") (pintype "passive"))
      (node (ref "U2") (pin "12") (pinfunction "VSSA_12") (pintype "power_in"))
      (node (ref "U8") (pin "2") (pinfunction "GND_2") (pintype "passive"))
    )
    (net (code "62") (name "AVCC") (class "Default")
      (node (ref "C21") (pin "2") (pinfunction "2_2") (pintype "passive"))
      (node (ref "C22") (pin "1") (pinfunction "1_1") (pintype "passive"))
      (node (ref "J3") (pin "6") (pinfunction "6_6") (pintype "passive"))
      (node (ref "TP4") (pin "1") (pintype "passive"))
      (node (ref "U2") (pin "13") (pinfunction "VDDA_13") (pintype "power_in"))
      (node (ref "U8") (pin "4") (pinfunction "N/C_4") (pintype "passive"))
      (node (ref "U8") (pin "5") (pinfunction "Vout_5") (pintype "passive"))
    )
    (net (code "63") (name "DCBUS") (class "Default")
      (node (ref "C11") (pin "1") (pinfunction "1_1") (pintype "passive"))
      (node (ref "C12") (pin "1") (pinfunction "1_1") (pintype "passive"))
      (node (ref "C13") (pin "1") (pinfunction "1_1") (pintype "passive"))
      (node (ref "C14") (pin "1") (pinfunction "1_1") (pintype "passive"))
      (node (ref "C15") (pin "1") (pinfunction "1_1") (pintype "passive"))
      (node (ref "C16") (pin "1") (pinfunction "1_1") (pintype "passive"))
      (node (ref "C17") (pin "1") (pinfunction "1_1") (pintype "passive"))
      (node (ref "C18") (pin "1") (pinfunction "1_1") (pintype "passive"))
      (node (ref "J7") (pin "1") (pinfunction "1_1") (pintype "passive"))
      (node (ref "J9") (pin "2") (pinfunction "2_2") (pintype "passive"))
      (node (ref "R6") (pin "2") (pinfunction "0_2") (pintype "passive"))
    )
    (net (code "64") (name "GND") (class "Default")
      (node (ref "*") (pin "2") (pinfunction "2_2") (pintype "passive"))
      (node (ref "C10") (pin "2") (pinfunction "2_2") (pintype "passive"))
      (node (ref "C19") (pin "1") (pinfunction "1_1") (pintype "passive"))
      (node (ref "C2") (pin "2") (pinfunction "2_2") (pintype "passive"))
      (node (ref "C20") (pin "1") (pinfunction "1_1") (pintype "passive"))
      (node (ref "C3") (pin "2") (pinfunction "2_2") (pintype "passive"))
      (node (ref "C4") (pin "1") (pinfunction "1_1") (pintype "passive"))
      (node (ref "C5") (pin "1") (pinfunction "1_1") (pintype "passive"))
      (node (ref "C6") (pin "1") (pinfunction "1_1") (pintype "passive"))
      (node (ref "C65") (pin "1") (pinfunction "1_1") (pintype "passive"))
      (node (ref "C7") (pin "2") (pinfunction "2_2") (pintype "passive"))
      (node (ref "C8") (pin "2") (pinfunction "2_2") (pintype "passive"))
      (node (ref "C9") (pin "2") (pinfunction "2_2") (pintype "passive"))
      (node (ref "J1") (pin "5") (pinfunction "GND_5") (pintype "passive"))
      (node (ref "J1") (pin "6") (pinfunction "6_6") (pintype "passive"))
      (node (ref "J1") (pin "7") (pinfunction "7_7") (pintype "passive"))
      (node (ref "J2") (pin "3") (pinfunction "3_3") (pintype "passive"))
      (node (ref "J3") (pin "2") (pinfunction "2_2") (pintype "passive"))
      (node (ref "J3") (pin "5") (pinfunction "5_5") (pintype "passive"))
      (node (ref "J4") (pin "12") (pinfunction "12_12") (pintype "passive"))
      (node (ref "J4") (pin "6") (pinfunction "6_6") (pintype "passive"))
      (node (ref "NT1") (pin "1") (pintype "passive"))
      (node (ref "R58") (pin "2") (pinfunction "0_2") (pintype "passive"))
      (node (ref "TP3") (pin "1") (pintype "passive"))
      (node (ref "U1") (pin "2") (pinfunction "GND_2") (pintype "passive"))
      (node (ref "U2") (pin "18") (pinfunction "VSS_18") (pintype "power_in"))
      (node (ref "U2") (pin "63") (pinfunction "VSS_63") (pintype "power_in"))
      (node (ref "U3") (pin "1") (pinfunction "GND_1") (pintype "passive"))
      (node (ref "XT1") (pin "G") (pintype "passive"))
    )
    (net (code "65") (name "Net-(*-Pad4)") (class "Default")
      (node (ref "*") (pin "4") (pinfunction "4_4") (pintype "passive"))
      (node (ref "R5") (pin "1") (pinfunction "0_1") (pintype "passive"))
    )
    (net (code "66") (name "Net-(J1-D+)") (class "Default")
      (node (ref "J1") (pin "3") (pinfunction "D+_3") (pintype "passive"))
      (node (ref "R3") (pin "2") (pinfunction "0_2") (pintype "passive"))
      (node (ref "TP2") (pin "1") (pintype "passive"))
    )
    (net (code "67") (name "Net-(J1-D-)") (class "Default")
      (node (ref "J1") (pin "2") (pinfunction "D-_2") (pintype "passive"))
      (node (ref "R1") (pin "2") (pinfunction "0_2") (pintype "passive"))
      (node (ref "TP1") (pin "1") (pintype "passive"))
    )
    (net (code "68") (name "Net-(J2-Pad2)") (class "Default")
      (node (ref "J2") (pin "2") (pinfunction "2_2") (pintype "passive"))
      (node (ref "R2") (pin "1") (pinfunction "0_1") (pintype "passive"))
    )
    (net (code "69") (name "Net-(J2-Pad4)") (class "Default")
      (node (ref "J2") (pin "4") (pinfunction "4_4") (pintype "passive"))
      (node (ref "R4") (pin "1") (pinfunction "0_1") (pintype "passive"))
    )
    (net (code "70") (name "Net-(LED1-PadK)") (class "Default")
      (node (ref "LED1") (pin "K") (pinfunction "K_K") (pintype "passive"))
      (node (ref "R58") (pin "1") (pinfunction "0_1") (pintype "passive"))
    )
    (net (code "71") (name "Net-(U2A-PH0-OSC_IN(PH0))") (class "Default")
      (node (ref "C3") (pin "1") (pinfunction "1_1") (pintype "passive"))
      (node (ref "U2") (pin "5") (pinfunction "PH0-OSC_IN(PH0)_5") (pintype "bidirectional"))
      (node (ref "XT1") (pin "3") (pintype "passive"))
    )
    (net (code "72") (name "Net-(U2A-PH1-OSC_OUT(PH1))") (class "Default")
      (node (ref "C2") (pin "1") (pinfunction "1_1") (pintype "passive"))
      (node (ref "U2") (pin "6") (pinfunction "PH1-OSC_OUT(PH1)_6") (pintype "bidirectional"))
      (node (ref "XT1") (pin "1") (pintype "passive"))
    )
    (net (code "73") (name "Net-(U2A-VCAP_1)") (class "Default")
      (node (ref "C5") (pin "2") (pinfunction "2_2") (pintype "passive"))
      (node (ref "U2") (pin "31") (pinfunction "VCAP_1_31") (pintype "power_in"))
    )
    (net (code "74") (name "Net-(U2A-VCAP_2)") (class "Default")
      (node (ref "C4") (pin "2") (pinfunction "2_2") (pintype "passive"))
      (node (ref "U2") (pin "47") (pinfunction "VCAP_2_47") (pintype "power_in"))
    )
    (net (code "75") (name "PGND") (class "Default")
      (node (ref "C11") (pin "2") (pinfunction "2_2") (pintype "passive"))
      (node (ref "C12") (pin "2") (pinfunction "2_2") (pintype "passive"))
      (node (ref "C13") (pin "2") (pinfunction "2_2") (pintype "passive"))
      (node (ref "C14") (pin "2") (pinfunction "2_2") (pintype "passive"))
      (node (ref "C15") (pin "2") (pinfunction "2_2") (pintype "passive"))
      (node (ref "C16") (pin "2") (pinfunction "2_2") (pintype "passive"))
      (node (ref "C17") (pin "2") (pinfunction "2_2") (pintype "passive"))
      (node (ref "C18") (pin "2") (pinfunction "2_2") (pintype "passive"))
      (node (ref "J8") (pin "1") (pinfunction "1_1") (pintype "passive"))
      (node (ref "J9") (pin "1") (pinfunction "1_1") (pintype "passive"))
    )
    (net (code "76") (name "VCC") (class "Default")
      (node (ref "C10") (pin "1") (pinfunction "1_1") (pintype "passive"))
      (node (ref "C19") (pin "2") (pinfunction "2_2") (pintype "passive"))
      (node (ref "C20") (pin "2") (pinfunction "2_2") (pintype "passive"))
      (node (ref "C7") (pin "1") (pinfunction "1_1") (pintype "passive"))
      (node (ref "C8") (pin "1") (pinfunction "1_1") (pintype "passive"))
      (node (ref "C9") (pin "1") (pinfunction "1_1") (pintype "passive"))
      (node (ref "J2") (pin "1") (pinfunction "1_1") (pintype "passive"))
      (node (ref "J3") (pin "1") (pinfunction "1_1") (pintype "passive"))
      (node (ref "J4") (pin "1") (pinfunction "1_1") (pintype "passive"))
      (node (ref "J4") (pin "7") (pinfunction "7_7") (pintype "passive"))
      (node (ref "LED1") (pin "A") (pinfunction "A_A") (pintype "passive"))
      (node (ref "R10") (pin "2") (pinfunction "0_2") (pintype "passive"))
      (node (ref "R11") (pin "2") (pinfunction "0_2") (pintype "passive"))
      (node (ref "R32") (pin "1") (pinfunction "0_1") (pintype "passive"))
      (node (ref "R33") (pin "1") (pinfunction "0_1") (pintype "passive"))
      (node (ref "R34") (pin "1") (pinfunction "0_1") (pintype "passive"))
      (node (ref "R8") (pin "2") (pinfunction "0_2") (pintype "passive"))
      (node (ref "R9") (pin "2") (pinfunction "0_2") (pintype "passive"))
      (node (ref "U1") (pin "3") (pinfunction "VCC_3") (pintype "passive"))
      (node (ref "U2") (pin "1") (pinfunction "VBAT_1") (pintype "power_in"))
      (node (ref "U2") (pin "19") (pinfunction "VDD_19") (pintype "power_in"))
      (node (ref "U2") (pin "32") (pinfunction "VDD_32") (pintype "power_in"))
      (node (ref "U2") (pin "48") (pinfunction "VDD_48") (pintype "power_in"))
      (node (ref "U2") (pin "64") (pinfunction "VDD_64") (pintype "power_in"))
      (node (ref "U3") (pin "2") (pinfunction "Vout_2") (pintype "passive"))
      (node (ref "U3") (pin "4") (pinfunction "Vout_(tab)_4") (pintype "passive"))
    )
    (net (code "77") (name "unconnected-(J1-ID-Pad4)") (class "Default")
      (node (ref "J1") (pin "4") (pinfunction "ID_4") (pintype "passive"))
    )
    (net (code "78") (name "unconnected-(J1-VCC-Pad1)") (class "Default")
      (node (ref "J1") (pin "1") (pinfunction "VCC_1") (pintype "passive"))
    )
    (net (code "79") (name "unconnected-(U1-NC-Pad5)") (class "Default")
      (node (ref "U1") (pin "5") (pinfunction "NC_5") (pintype "passive"))
    )
    (net (code "80") (name "unconnected-(U1-NC-Pad8)") (class "Default")
      (node (ref "U1") (pin "8") (pinfunction "NC_8") (pintype "passive"))
    )
  )
)
